# 03_PWR.net
KiCad netlist of a schematic drawn in Altium Designer
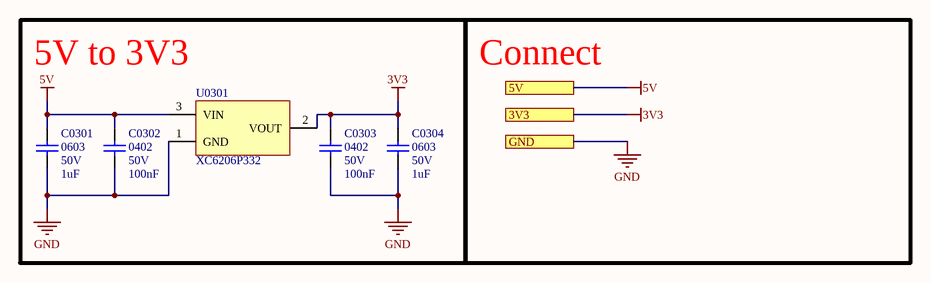
[diagram p0: 03_PWR.SchDoc]

(export (version "E")
  (design (tool "Eeschema 10.0.6"))
  (components
    (comp (ref "C0301")
      (value "Cap")
      (footprint "C0603")
      (fields (field (name "SIZE") "0603") (field (name "VOLT") "50V") (field (name "CAP") "1uF"))
      (libsource (lib "LCR") (part "Cap"))
    )
    (comp (ref "C0302")
      (value "Cap")
      (footprint "C0402")
      (fields (field (name "SIZE") "0402") (field (name "VOLT") "50V") (field (name "CAP") "100nF"))
      (libsource (lib "LCR") (part "Cap"))
    )
    (comp (ref "C0303")
      (value "Cap")
      (footprint "C0402")
      (fields (field (name "SIZE") "0402") (field (name "VOLT") "50V") (field (name "CAP") "100nF"))
      (libsource (lib "LCR") (part "Cap"))
    )
    (comp (ref "C0304")
      (value "Cap")
      (footprint "C0603")
      (fields (field (name "SIZE") "0603") (field (name "VOLT") "50V") (field (name "CAP") "1uF"))
      (libsource (lib "LCR") (part "Cap"))
    )
    (comp (ref "U0301")
      (value "XC6206P332")
      (footprint "SOT23-3L")
      (description "VIN < 6V")
      (libsource (lib "PwrIC") (part "XC6206"))
    )
  )
  (nets
    (net (code "1") (name "3V3") (class "Default")
      (node (ref "C0303") (pin "2") (pinfunction "2_2") (pintype "passive"))
      (node (ref "C0304") (pin "2") (pinfunction "2_2") (pintype "passive"))
      (node (ref "U0301") (pin "2") (pinfunction "VOUT_2") (pintype "passive"))
    )
    (net (code "2") (name "5V") (class "Default")
      (node (ref "C0301") (pin "2") (pinfunction "2_2") (pintype "passive"))
      (node (ref "C0302") (pin "2") (pinfunction "2_2") (pintype "passive"))
      (node (ref "U0301") (pin "3") (pinfunction "VIN_3") (pintype "passive"))
    )
    (net (code "3") (name "GND") (class "Default")
      (node (ref "C0301") (pin "1") (pinfunction "1_1") (pintype "passive"))
      (node (ref "C0302") (pin "1") (pinfunction "1_1") (pintype "passive"))
      (node (ref "C0303") (pin "1") (pinfunction "1_1") (pintype "passive"))
      (node (ref "C0304") (pin "1") (pinfunction "1_1") (pintype "passive"))
      (node (ref "U0301") (pin "1") (pinfunction "GND_1") (pintype "passive"))
    )
  )
)
